# slide-control.net
KiCad netlist of a schematic drawn in EAGLE
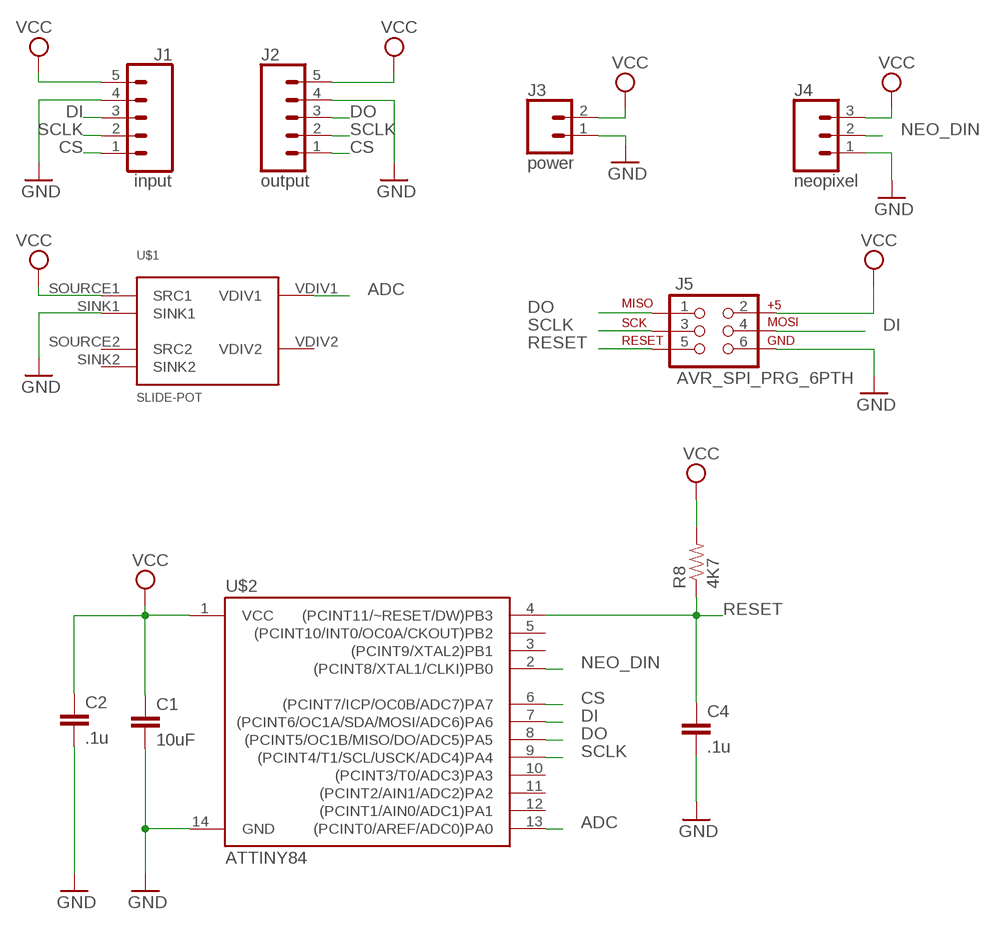
[diagram p0: schematic, sheet 1]

(export (version "E")
  (design (tool "Eeschema 10.0.6"))
  (components
    (comp (ref "C1")
      (value "10uF")
      (footprint "eagle-import:1206")
      (libsource (lib "eagle-import") (part "10UF-1206-6.3V-20%"))
    )
    (comp (ref "C2")
      (value ".1u")
      (footprint "eagle-import:0805")
      (libsource (lib "eagle-import") (part "CAP0805"))
    )
    (comp (ref "C4")
      (value ".1u")
      (footprint "eagle-import:0805")
      (libsource (lib "eagle-import") (part "CAP0805"))
    )
    (comp (ref "J1")
      (value "input")
      (footprint "eagle-import:1X05")
      (libsource (lib "eagle-import") (part "CONN_05"))
    )
    (comp (ref "J2")
      (value "output")
      (footprint "eagle-import:1X05")
      (libsource (lib "eagle-import") (part "CONN_05"))
    )
    (comp (ref "J3")
      (value "power")
      (footprint "eagle-import:1X02")
      (libsource (lib "eagle-import") (part "CONN_02"))
    )
    (comp (ref "J4")
      (value "neopixel")
      (footprint "eagle-import:1X03")
      (libsource (lib "eagle-import") (part "CONN_03"))
    )
    (comp (ref "J5")
      (value "AVR_SPI_PRG_6PTH")
      (footprint "eagle-import:2X3")
      (libsource (lib "eagle-import") (part "AVR_SPI_PRG_6PTH"))
    )
    (comp (ref "R8")
      (value "4K7")
      (footprint "eagle-import:0805")
      (libsource (lib "eagle-import") (part "RESISTOR"))
    )
    (comp (ref "U$1")
      (value "SLIDE-POT")
      (footprint "eagle-import:SLIDE-POT")
      (libsource (lib "eagle-import") (part "SLIDE-POT"))
    )
    (comp (ref "U$2")
      (value "ATTINY84")
      (footprint "eagle-import:SO14")
      (libsource (lib "eagle-import") (part "ATTINY84"))
    )
  )
  (nets
    (net (code "1") (name "/ADC") (class "Default")
      (node (ref "U$1") (pin "VDIV1") (pinfunction "VDIV1_VDIV1") (pintype "bidirectional"))
      (node (ref "U$2") (pin "13") (pinfunction "(PCINT0/AREF/ADC0)PA0_13") (pintype "bidirectional"))
    )
    (net (code "2") (name "/CS") (class "Default")
      (node (ref "J1") (pin "1") (pinfunction "1_1") (pintype "passive"))
      (node (ref "J2") (pin "1") (pinfunction "1_1") (pintype "passive"))
      (node (ref "U$2") (pin "6") (pinfunction "(PCINT7/ICP/OC0B/ADC7)PA7_6") (pintype "bidirectional"))
    )
    (net (code "3") (name "/DI") (class "Default")
      (node (ref "J1") (pin "3") (pinfunction "3_3") (pintype "passive"))
      (node (ref "J5") (pin "4") (pinfunction "4_4") (pintype "passive"))
      (node (ref "U$2") (pin "7") (pinfunction "(PCINT6/OC1A/SDA/MOSI/ADC6)PA6_7") (pintype "bidirectional"))
    )
    (net (code "4") (name "/DO") (class "Default")
      (node (ref "J2") (pin "3") (pinfunction "3_3") (pintype "passive"))
      (node (ref "J5") (pin "1") (pinfunction "1_1") (pintype "passive"))
      (node (ref "U$2") (pin "8") (pinfunction "(PCINT5/OC1B/MISO/DO/ADC5)PA5_8") (pintype "bidirectional"))
    )
    (net (code "5") (name "/NEO_DIN") (class "Default")
      (node (ref "J4") (pin "2") (pinfunction "2_2") (pintype "passive"))
      (node (ref "U$2") (pin "2") (pinfunction "(PCINT8/XTAL1/CLKI)PB0_2") (pintype "bidirectional"))
    )
    (net (code "6") (name "/RESET") (class "Default")
      (node (ref "C4") (pin "1") (pinfunction "1_1") (pintype "passive"))
      (node (ref "J5") (pin "5") (pinfunction "5_5") (pintype "passive"))
      (node (ref "R8") (pin "1") (pinfunction "1_1") (pintype "passive"))
      (node (ref "U$2") (pin "4") (pinfunction "(PCINT11/~{RESET/DW})PB3_4") (pintype "bidirectional"))
    )
    (net (code "7") (name "/SCLK") (class "Default")
      (node (ref "J1") (pin "2") (pinfunction "2_2") (pintype "passive"))
      (node (ref "J2") (pin "2") (pinfunction "2_2") (pintype "passive"))
      (node (ref "J5") (pin "3") (pinfunction "3_3") (pintype "passive"))
      (node (ref "U$2") (pin "9") (pinfunction "(PCINT4/T1/SCL/USCK/ADC4)PA4_9") (pintype "bidirectional"))
    )
    (net (code "8") (name "GND") (class "Default")
      (node (ref "C1") (pin "2") (pinfunction "2_2") (pintype "passive"))
      (node (ref "C2") (pin "2") (pinfunction "2_2") (pintype "passive"))
      (node (ref "C4") (pin "2") (pinfunction "2_2") (pintype "passive"))
      (node (ref "J1") (pin "4") (pinfunction "4_4") (pintype "passive"))
      (node (ref "J2") (pin "4") (pinfunction "4_4") (pintype "passive"))
      (node (ref "J3") (pin "1") (pinfunction "1_1") (pintype "passive"))
      (node (ref "J4") (pin "1") (pinfunction "1_1") (pintype "passive"))
      (node (ref "J5") (pin "6") (pinfunction "6_6") (pintype "passive"))
      (node (ref "U$1") (pin "SINK1") (pinfunction "SINK1_SINK1") (pintype "bidirectional"))
      (node (ref "U$2") (pin "14") (pinfunction "GND_14") (pintype "bidirectional"))
    )
    (net (code "9") (name "VCC") (class "Default")
      (node (ref "C1") (pin "1") (pinfunction "1_1") (pintype "passive"))
      (node (ref "C2") (pin "1") (pinfunction "1_1") (pintype "passive"))
      (node (ref "J1") (pin "5") (pinfunction "5_5") (pintype "passive"))
      (node (ref "J2") (pin "5") (pinfunction "5_5") (pintype "passive"))
      (node (ref "J3") (pin "2") (pinfunction "2_2") (pintype "passive"))
      (node (ref "J4") (pin "3") (pinfunction "3_3") (pintype "passive"))
      (node (ref "J5") (pin "2") (pinfunction "2_2") (pintype "passive"))
      (node (ref "R8") (pin "2") (pinfunction "2_2") (pintype "passive"))
      (node (ref "U$1") (pin "SOURCE1") (pinfunction "SRC1_SOURCE1") (pintype "bidirectional"))
      (node (ref "U$2") (pin "1") (pinfunction "VCC_1") (pintype "bidirectional"))
    )
    (net (code "10") (name "unconnected-(U$1-PadSINK2)") (class "Default")
      (node (ref "U$1") (pin "SINK2") (pinfunction "SINK2_SINK2") (pintype "bidirectional"))
    )
    (net (code "11") (name "unconnected-(U$1-PadVDIV2)") (class "Default")
      (node (ref "U$1") (pin "VDIV2") (pinfunction "VDIV2_VDIV2") (pintype "bidirectional"))
    )
    (net (code "12") (name "unconnected-(U$1-SRC2-PadSOURCE2)") (class "Default")
      (node (ref "U$1") (pin "SOURCE2") (pinfunction "SRC2_SOURCE2") (pintype "bidirectional"))
    )
    (net (code "13") (name "unconnected-(U$2-(PCINT1{slash}AIN0{slash}ADC1)PA1-Pad12)") (class "Default")
      (node (ref "U$2") (pin "12") (pinfunction "(PCINT1/AIN0/ADC1)PA1_12") (pintype "bidirectional"))
    )
    (net (code "14") (name "unconnected-(U$2-(PCINT2{slash}AIN1{slash}ADC2)PA2-Pad11)") (class "Default")
      (node (ref "U$2") (pin "11") (pinfunction "(PCINT2/AIN1/ADC2)PA2_11") (pintype "bidirectional"))
    )
    (net (code "15") (name "unconnected-(U$2-(PCINT3{slash}T0{slash}ADC3)PA3-Pad10)") (class "Default")
      (node (ref "U$2") (pin "10") (pinfunction "(PCINT3/T0/ADC3)PA3_10") (pintype "bidirectional"))
    )
    (net (code "16") (name "unconnected-(U$2-(PCINT9{slash}XTAL2)PB1-Pad3)") (class "Default")
      (node (ref "U$2") (pin "3") (pinfunction "(PCINT9/XTAL2)PB1_3") (pintype "bidirectional"))
    )
    (net (code "17") (name "unconnected-(U$2-(PCINT10{slash}INT0{slash}OC0A{slash}CKOUT)PB2-Pad5)") (class "Default")
      (node (ref "U$2") (pin "5") (pinfunction "(PCINT10/INT0/OC0A/CKOUT)PB2_5") (pintype "bidirectional"))
    )
  )
)
